# Sheet1.net
KiCad netlist of a schematic drawn in Altium Designer
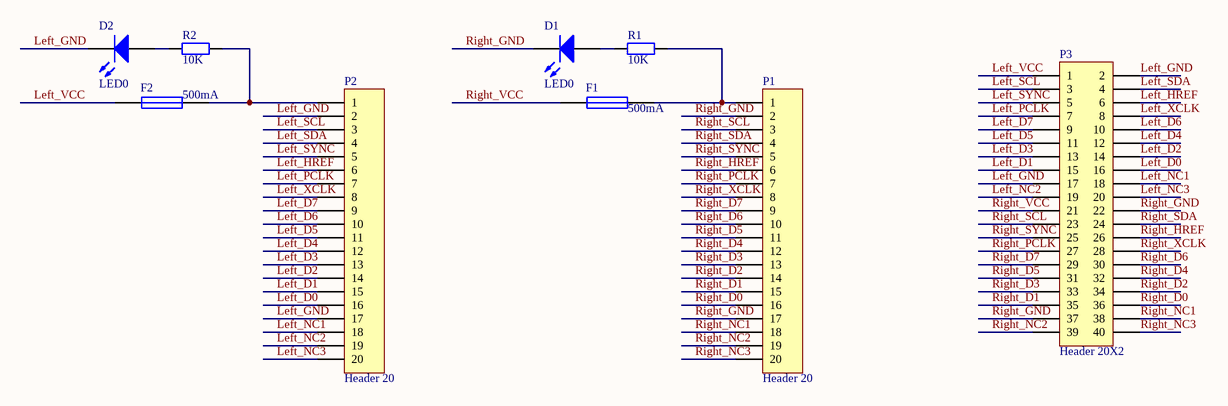
[diagram p0: Sheet1.SchDoc]

(export (version "E")
  (design (tool "Eeschema 10.0.6"))
  (components
    (comp (ref "D1")
      (value "LED0")
      (footprint "LED0805绿")
      (description "Typical INFRARED GaAs LED")
      (fields (field (name "PUBLISHER") "Altium Limited"))
      (libsource (lib "Miscellaneous Devices") (part "LED0"))
    )
    (comp (ref "D2")
      (value "LED0")
      (footprint "LED0805绿")
      (description "Typical INFRARED GaAs LED")
      (fields (field (name "PUBLISHER") "Altium Limited"))
      (libsource (lib "Miscellaneous Devices") (part "LED0"))
    )
    (comp (ref "F1")
      (value "500mA")
      (footprint "R0805")
      (description "Fuse")
      (fields (field (name "PUBLISHER") "Altium Limited"))
      (libsource (lib "Miscellaneous Devices") (part "Fuse 1"))
    )
    (comp (ref "F2")
      (value "500mA")
      (footprint "R0805")
      (description "Fuse")
      (fields (field (name "PUBLISHER") "Altium Limited"))
      (libsource (lib "Miscellaneous Devices") (part "Fuse 1"))
    )
    (comp (ref "P1")
      (value "Header 20")
      (footprint "FPC20Pin")
      (description "Header, 20-Pin")
      (fields (field (name "PUBLISHER") "Altium Limited"))
      (libsource (lib "Miscellaneous Connectors") (part "Header 20"))
    )
    (comp (ref "P2")
      (value "Header 20")
      (footprint "FPC20Pin")
      (description "Header, 20-Pin")
      (fields (field (name "PUBLISHER") "Altium Limited"))
      (libsource (lib "Miscellaneous Connectors") (part "Header 20"))
    )
    (comp (ref "P3")
      (value "Header 20X2")
      (footprint "FPC_40pin_05mm")
      (description "Header, 20-Pin, Dual row")
      (fields (field (name "PUBLISHER") "Altium Limited"))
      (libsource (lib "Miscellaneous Connectors") (part "Header 20X2"))
    )
    (comp (ref "R1")
      (value "10K")
      (footprint "R0805")
      (description "Resistor")
      (fields (field (name "Comment") "Res2") (field (name "PUBLISHER") "Altium Limited"))
      (libsource (lib "Miscellaneous Devices") (part "Res2"))
    )
    (comp (ref "R2")
      (value "10K")
      (footprint "R0805")
      (description "Resistor")
      (fields (field (name "Comment") "Res2") (field (name "PUBLISHER") "Altium Limited"))
      (libsource (lib "Miscellaneous Devices") (part "Res2"))
    )
  )
  (nets
    (net (code "1") (name "/Left_D0") (class "Default")
      (node (ref "P2") (pin "16") (pinfunction "16_16") (pintype "passive"))
      (node (ref "P3") (pin "16") (pinfunction "16_16") (pintype "passive"))
    )
    (net (code "2") (name "/Left_D1") (class "Default")
      (node (ref "P2") (pin "15") (pinfunction "15_15") (pintype "passive"))
      (node (ref "P3") (pin "15") (pinfunction "15_15") (pintype "passive"))
    )
    (net (code "3") (name "/Left_D2") (class "Default")
      (node (ref "P2") (pin "14") (pinfunction "14_14") (pintype "passive"))
      (node (ref "P3") (pin "14") (pinfunction "14_14") (pintype "passive"))
    )
    (net (code "4") (name "/Left_D3") (class "Default")
      (node (ref "P2") (pin "13") (pinfunction "13_13") (pintype "passive"))
      (node (ref "P3") (pin "13") (pinfunction "13_13") (pintype "passive"))
    )
    (net (code "5") (name "/Left_D4") (class "Default")
      (node (ref "P2") (pin "12") (pinfunction "12_12") (pintype "passive"))
      (node (ref "P3") (pin "12") (pinfunction "12_12") (pintype "passive"))
    )
    (net (code "6") (name "/Left_D5") (class "Default")
      (node (ref "P2") (pin "11") (pinfunction "11_11") (pintype "passive"))
      (node (ref "P3") (pin "11") (pinfunction "11_11") (pintype "passive"))
    )
    (net (code "7") (name "/Left_D6") (class "Default")
      (node (ref "P2") (pin "10") (pinfunction "10_10") (pintype "passive"))
      (node (ref "P3") (pin "10") (pinfunction "10_10") (pintype "passive"))
    )
    (net (code "8") (name "/Left_D7") (class "Default")
      (node (ref "P2") (pin "9") (pinfunction "9_9") (pintype "passive"))
      (node (ref "P3") (pin "9") (pinfunction "9_9") (pintype "passive"))
    )
    (net (code "9") (name "/Left_GND") (class "Default")
      (node (ref "D2") (pin "2") (pinfunction "K_2") (pintype "passive"))
      (node (ref "P2") (pin "17") (pinfunction "17_17") (pintype "passive"))
      (node (ref "P2") (pin "2") (pinfunction "2_2") (pintype "passive"))
      (node (ref "P3") (pin "17") (pinfunction "17_17") (pintype "passive"))
      (node (ref "P3") (pin "2") (pinfunction "2_2") (pintype "passive"))
    )
    (net (code "10") (name "/Left_HREF") (class "Default")
      (node (ref "P2") (pin "6") (pinfunction "6_6") (pintype "passive"))
      (node (ref "P3") (pin "6") (pinfunction "6_6") (pintype "passive"))
    )
    (net (code "11") (name "/Left_NC1") (class "Default")
      (node (ref "P2") (pin "18") (pinfunction "18_18") (pintype "passive"))
      (node (ref "P3") (pin "18") (pinfunction "18_18") (pintype "passive"))
    )
    (net (code "12") (name "/Left_NC2") (class "Default")
      (node (ref "P2") (pin "19") (pinfunction "19_19") (pintype "passive"))
      (node (ref "P3") (pin "19") (pinfunction "19_19") (pintype "passive"))
    )
    (net (code "13") (name "/Left_NC3") (class "Default")
      (node (ref "P2") (pin "20") (pinfunction "20_20") (pintype "passive"))
      (node (ref "P3") (pin "20") (pinfunction "20_20") (pintype "passive"))
    )
    (net (code "14") (name "/Left_PCLK") (class "Default")
      (node (ref "P2") (pin "7") (pinfunction "7_7") (pintype "passive"))
      (node (ref "P3") (pin "7") (pinfunction "7_7") (pintype "passive"))
    )
    (net (code "15") (name "/Left_SCL") (class "Default")
      (node (ref "P2") (pin "3") (pinfunction "3_3") (pintype "passive"))
      (node (ref "P3") (pin "3") (pinfunction "3_3") (pintype "passive"))
    )
    (net (code "16") (name "/Left_SDA") (class "Default")
      (node (ref "P2") (pin "4") (pinfunction "4_4") (pintype "passive"))
      (node (ref "P3") (pin "4") (pinfunction "4_4") (pintype "passive"))
    )
    (net (code "17") (name "/Left_SYNC") (class "Default")
      (node (ref "P2") (pin "5") (pinfunction "5_5") (pintype "passive"))
      (node (ref "P3") (pin "5") (pinfunction "5_5") (pintype "passive"))
    )
    (net (code "18") (name "/Left_VCC") (class "Default")
      (node (ref "F2") (pin "1") (pinfunction "1_1") (pintype "passive"))
      (node (ref "P3") (pin "1") (pinfunction "1_1") (pintype "passive"))
    )
    (net (code "19") (name "/Left_XCLK") (class "Default")
      (node (ref "P2") (pin "8") (pinfunction "8_8") (pintype "passive"))
      (node (ref "P3") (pin "8") (pinfunction "8_8") (pintype "passive"))
    )
    (net (code "20") (name "/Right_D0") (class "Default")
      (node (ref "P1") (pin "16") (pinfunction "16_16") (pintype "passive"))
      (node (ref "P3") (pin "36") (pinfunction "36_36") (pintype "passive"))
    )
    (net (code "21") (name "/Right_D1") (class "Default")
      (node (ref "P1") (pin "15") (pinfunction "15_15") (pintype "passive"))
      (node (ref "P3") (pin "35") (pinfunction "35_35") (pintype "passive"))
    )
    (net (code "22") (name "/Right_D2") (class "Default")
      (node (ref "P1") (pin "14") (pinfunction "14_14") (pintype "passive"))
      (node (ref "P3") (pin "34") (pinfunction "34_34") (pintype "passive"))
    )
    (net (code "23") (name "/Right_D3") (class "Default")
      (node (ref "P1") (pin "13") (pinfunction "13_13") (pintype "passive"))
      (node (ref "P3") (pin "33") (pinfunction "33_33") (pintype "passive"))
    )
    (net (code "24") (name "/Right_D4") (class "Default")
      (node (ref "P1") (pin "12") (pinfunction "12_12") (pintype "passive"))
      (node (ref "P3") (pin "32") (pinfunction "32_32") (pintype "passive"))
    )
    (net (code "25") (name "/Right_D5") (class "Default")
      (node (ref "P1") (pin "11") (pinfunction "11_11") (pintype "passive"))
      (node (ref "P3") (pin "31") (pinfunction "31_31") (pintype "passive"))
    )
    (net (code "26") (name "/Right_D6") (class "Default")
      (node (ref "P1") (pin "10") (pinfunction "10_10") (pintype "passive"))
      (node (ref "P3") (pin "30") (pinfunction "30_30") (pintype "passive"))
    )
    (net (code "27") (name "/Right_D7") (class "Default")
      (node (ref "P1") (pin "9") (pinfunction "9_9") (pintype "passive"))
      (node (ref "P3") (pin "29") (pinfunction "29_29") (pintype "passive"))
    )
    (net (code "28") (name "/Right_GND") (class "Default")
      (node (ref "D1") (pin "2") (pinfunction "K_2") (pintype "passive"))
      (node (ref "P1") (pin "17") (pinfunction "17_17") (pintype "passive"))
      (node (ref "P1") (pin "2") (pinfunction "2_2") (pintype "passive"))
      (node (ref "P3") (pin "22") (pinfunction "22_22") (pintype "passive"))
      (node (ref "P3") (pin "37") (pinfunction "37_37") (pintype "passive"))
    )
    (net (code "29") (name "/Right_HREF") (class "Default")
      (node (ref "P1") (pin "6") (pinfunction "6_6") (pintype "passive"))
      (node (ref "P3") (pin "26") (pinfunction "26_26") (pintype "passive"))
    )
    (net (code "30") (name "/Right_NC1") (class "Default")
      (node (ref "P1") (pin "18") (pinfunction "18_18") (pintype "passive"))
      (node (ref "P3") (pin "38") (pinfunction "38_38") (pintype "passive"))
    )
    (net (code "31") (name "/Right_NC2") (class "Default")
      (node (ref "P1") (pin "19") (pinfunction "19_19") (pintype "passive"))
      (node (ref "P3") (pin "39") (pinfunction "39_39") (pintype "passive"))
    )
    (net (code "32") (name "/Right_NC3") (class "Default")
      (node (ref "P1") (pin "20") (pinfunction "20_20") (pintype "passive"))
      (node (ref "P3") (pin "40") (pinfunction "40_40") (pintype "passive"))
    )
    (net (code "33") (name "/Right_PCLK") (class "Default")
      (node (ref "P1") (pin "7") (pinfunction "7_7") (pintype "passive"))
      (node (ref "P3") (pin "27") (pinfunction "27_27") (pintype "passive"))
    )
    (net (code "34") (name "/Right_SCL") (class "Default")
      (node (ref "P1") (pin "3") (pinfunction "3_3") (pintype "passive"))
      (node (ref "P3") (pin "23") (pinfunction "23_23") (pintype "passive"))
    )
    (net (code "35") (name "/Right_SDA") (class "Default")
      (node (ref "P1") (pin "4") (pinfunction "4_4") (pintype "passive"))
      (node (ref "P3") (pin "24") (pinfunction "24_24") (pintype "passive"))
    )
    (net (code "36") (name "/Right_SYNC") (class "Default")
      (node (ref "P1") (pin "5") (pinfunction "5_5") (pintype "passive"))
      (node (ref "P3") (pin "25") (pinfunction "25_25") (pintype "passive"))
    )
    (net (code "37") (name "/Right_VCC") (class "Default")
      (node (ref "F1") (pin "1") (pinfunction "1_1") (pintype "passive"))
      (node (ref "P3") (pin "21") (pinfunction "21_21") (pintype "passive"))
    )
    (net (code "38") (name "/Right_XCLK") (class "Default")
      (node (ref "P1") (pin "8") (pinfunction "8_8") (pintype "passive"))
      (node (ref "P3") (pin "28") (pinfunction "28_28") (pintype "passive"))
    )
    (net (code "39") (name "Net-(D1-A)") (class "Default")
      (node (ref "D1") (pin "1") (pinfunction "A_1") (pintype "passive"))
      (node (ref "R1") (pin "2") (pinfunction "2_2") (pintype "passive"))
    )
    (net (code "40") (name "Net-(D2-A)") (class "Default")
      (node (ref "D2") (pin "1") (pinfunction "A_1") (pintype "passive"))
      (node (ref "R2") (pin "2") (pinfunction "2_2") (pintype "passive"))
    )
    (net (code "41") (name "Net-(F1-Pad2)") (class "Default")
      (node (ref "F1") (pin "2") (pinfunction "2_2") (pintype "passive"))
      (node (ref "P1") (pin "1") (pinfunction "1_1") (pintype "passive"))
      (node (ref "R1") (pin "1") (pinfunction "1_1") (pintype "passive"))
    )
    (net (code "42") (name "Net-(F2-Pad2)") (class "Default")
      (node (ref "F2") (pin "2") (pinfunction "2_2") (pintype "passive"))
      (node (ref "P2") (pin "1") (pinfunction "1_1") (pintype "passive"))
      (node (ref "R2") (pin "1") (pinfunction "1_1") (pintype "passive"))
    )
  )
)
